# hc-isp-echo.net
KiCad netlist of a schematic drawn in EAGLE
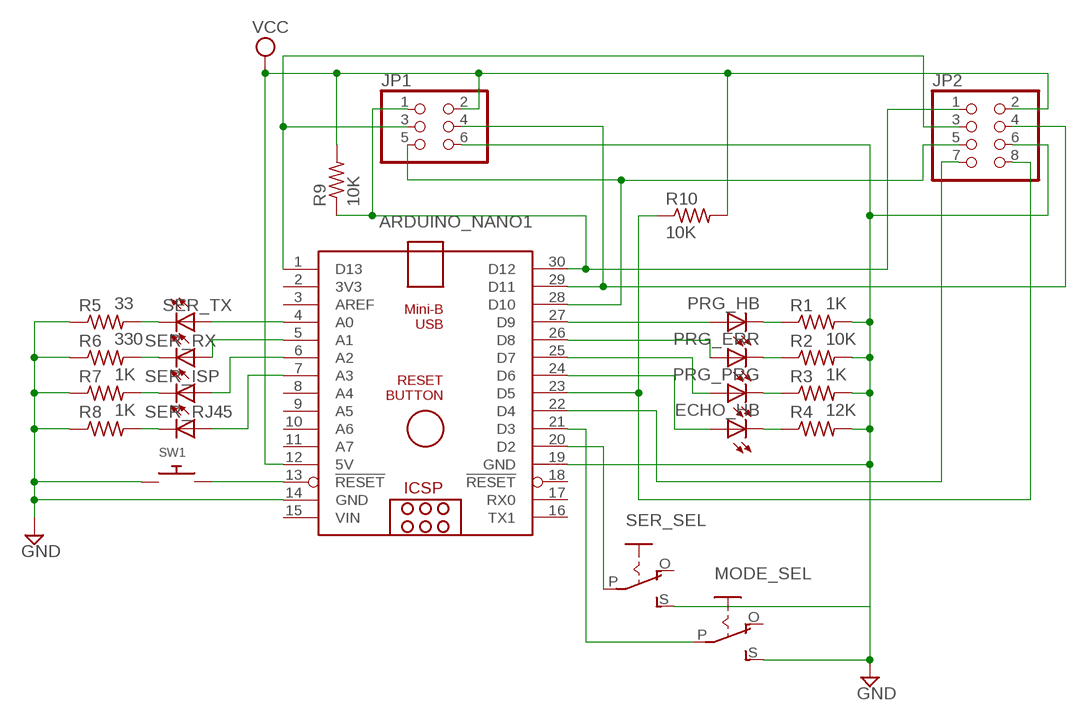
[diagram p0: schematic, sheet 1]

(export (version "E")
  (design (tool "Eeschema 10.0.6"))
  (components
    (comp (ref "ARDUINO_NANO1")
      (value "ARDUINO_NANO_HCARDUINO_NANO_NO_HOLE")
      (footprint "eagle-import:ARDUINO_NANO_NO_HOLE")
      (libsource (lib "eagle-import") (part "ARDUINO_NANO_HCARDUINO_NANO_NO_HOLE"))
    )
    (comp (ref "ECHO_HB")
      (value "LED5MM")
      (footprint "eagle-import:LED5MM")
      (libsource (lib "eagle-import") (part "LED5MM"))
    )
    (comp (ref "JP1")
      (value "PINHD-2X3")
      (footprint "eagle-import:2X03")
      (libsource (lib "eagle-import") (part "PINHD-2X3"))
    )
    (comp (ref "JP2")
      (value "PINHD-2X4")
      (footprint "eagle-import:2X04")
      (libsource (lib "eagle-import") (part "PINHD-2X4"))
    )
    (comp (ref "MODE_SEL")
      (value "EG1218S")
      (footprint "eagle-import:EG1218")
      (libsource (lib "eagle-import") (part "EG1218S"))
    )
    (comp (ref "PRG_ERR")
      (value "LED5MM")
      (footprint "eagle-import:LED5MM")
      (libsource (lib "eagle-import") (part "LED5MM"))
    )
    (comp (ref "PRG_HB")
      (value "LED5MM")
      (footprint "eagle-import:LED5MM")
      (libsource (lib "eagle-import") (part "LED5MM"))
    )
    (comp (ref "PRG_PRG")
      (value "LED5MM")
      (footprint "eagle-import:LED5MM")
      (libsource (lib "eagle-import") (part "LED5MM"))
    )
    (comp (ref "R1")
      (value "1K")
      (footprint "eagle-import:0309_12")
      (libsource (lib "eagle-import") (part "R-US_0309/12"))
    )
    (comp (ref "R2")
      (value "10K")
      (footprint "eagle-import:0309_12")
      (libsource (lib "eagle-import") (part "R-US_0309/12"))
    )
    (comp (ref "R3")
      (value "1K")
      (footprint "eagle-import:0309_12")
      (libsource (lib "eagle-import") (part "R-US_0309/12"))
    )
    (comp (ref "R4")
      (value "12K")
      (footprint "eagle-import:0309_12")
      (libsource (lib "eagle-import") (part "R-US_0309/12"))
    )
    (comp (ref "R5")
      (value "33")
      (footprint "eagle-import:0309_12")
      (libsource (lib "eagle-import") (part "R-US_0309/12"))
    )
    (comp (ref "R6")
      (value "330")
      (footprint "eagle-import:0309_12")
      (libsource (lib "eagle-import") (part "R-US_0309/12"))
    )
    (comp (ref "R7")
      (value "1K")
      (footprint "eagle-import:0309_12")
      (libsource (lib "eagle-import") (part "R-US_0309/12"))
    )
    (comp (ref "R8")
      (value "1K")
      (footprint "eagle-import:0309_12")
      (libsource (lib "eagle-import") (part "R-US_0309/12"))
    )
    (comp (ref "R9")
      (value "10K")
      (footprint "eagle-import:0309_12")
      (libsource (lib "eagle-import") (part "R-US_0309/12"))
    )
    (comp (ref "R10")
      (value "10K")
      (footprint "eagle-import:0309_12")
      (libsource (lib "eagle-import") (part "R-US_0309/12"))
    )
    (comp (ref "SER_ISP")
      (value "LED5MM")
      (footprint "eagle-import:LED5MM")
      (libsource (lib "eagle-import") (part "LED5MM"))
    )
    (comp (ref "SER_RJ45")
      (value "LED5MM")
      (footprint "eagle-import:LED5MM")
      (libsource (lib "eagle-import") (part "LED5MM"))
    )
    (comp (ref "SER_RX")
      (value "LED5MM")
      (footprint "eagle-import:LED5MM")
      (libsource (lib "eagle-import") (part "LED5MM"))
    )
    (comp (ref "SER_SEL")
      (value "EG1218S")
      (footprint "eagle-import:EG1218")
      (libsource (lib "eagle-import") (part "EG1218S"))
    )
    (comp (ref "SER_TX")
      (value "LED5MM")
      (footprint "eagle-import:LED5MM")
      (libsource (lib "eagle-import") (part "LED5MM"))
    )
    (comp (ref "SW1")
      (value "SWITCH_PUSHBUTTONEVQ-PE")
      (footprint "eagle-import:TACT_PANA-EVQ")
      (libsource (lib "eagle-import") (part "SWITCH_PUSHBUTTONEVQ-PE"))
    )
  )
  (nets
    (net (code "1") (name "/VIN") (class "Default")
      (node (ref "ARDUINO_NANO1") (pin "15") (pinfunction "VIN_15") (pintype "power_in"))
    )
    (net (code "2") (name "GND") (class "Default")
      (node (ref "ARDUINO_NANO1") (pin "14") (pinfunction "GND_14") (pintype "power_in"))
      (node (ref "ARDUINO_NANO1") (pin "19") (pinfunction "GND_19") (pintype "power_in"))
      (node (ref "JP1") (pin "6") (pinfunction "6_6") (pintype "passive"))
      (node (ref "JP2") (pin "6") (pinfunction "6_6") (pintype "passive"))
      (node (ref "MODE_SEL") (pin "S") (pinfunction "S_S") (pintype "passive"))
      (node (ref "R1") (pin "2") (pinfunction "2_2") (pintype "passive"))
      (node (ref "R2") (pin "2") (pinfunction "2_2") (pintype "passive"))
      (node (ref "R3") (pin "2") (pinfunction "2_2") (pintype "passive"))
      (node (ref "R4") (pin "2") (pinfunction "2_2") (pintype "passive"))
      (node (ref "R5") (pin "1") (pinfunction "1_1") (pintype "passive"))
      (node (ref "R6") (pin "1") (pinfunction "1_1") (pintype "passive"))
      (node (ref "R7") (pin "1") (pinfunction "1_1") (pintype "passive"))
      (node (ref "R8") (pin "1") (pinfunction "1_1") (pintype "passive"))
      (node (ref "SER_SEL") (pin "S") (pinfunction "S_S") (pintype "passive"))
      (node (ref "SW1") (pin "P$1") (pinfunction "P$1_P$1") (pintype "passive"))
    )
    (net (code "3") (name "Net-(ARDUINO_NANO1-A0)") (class "Default")
      (node (ref "ARDUINO_NANO1") (pin "4") (pinfunction "A0_4") (pintype "bidirectional"))
      (node (ref "SER_TX") (pin "A") (pinfunction "A_A") (pintype "passive"))
    )
    (net (code "4") (name "Net-(ARDUINO_NANO1-A1)") (class "Default")
      (node (ref "ARDUINO_NANO1") (pin "5") (pinfunction "A1_5") (pintype "bidirectional"))
      (node (ref "SER_RX") (pin "A") (pinfunction "A_A") (pintype "passive"))
    )
    (net (code "5") (name "Net-(ARDUINO_NANO1-A2)") (class "Default")
      (node (ref "ARDUINO_NANO1") (pin "6") (pinfunction "A2_6") (pintype "bidirectional"))
      (node (ref "SER_ISP") (pin "A") (pinfunction "A_A") (pintype "passive"))
    )
    (net (code "6") (name "Net-(ARDUINO_NANO1-A3)") (class "Default")
      (node (ref "ARDUINO_NANO1") (pin "7") (pinfunction "A3_7") (pintype "bidirectional"))
      (node (ref "SER_RJ45") (pin "A") (pinfunction "A_A") (pintype "passive"))
    )
    (net (code "7") (name "Net-(ARDUINO_NANO1-D2)") (class "Default")
      (node (ref "ARDUINO_NANO1") (pin "20") (pinfunction "D2_20") (pintype "bidirectional"))
      (node (ref "SER_SEL") (pin "P") (pinfunction "P_P") (pintype "passive"))
    )
    (net (code "8") (name "Net-(ARDUINO_NANO1-D3)") (class "Default")
      (node (ref "ARDUINO_NANO1") (pin "21") (pinfunction "D3_21") (pintype "bidirectional"))
      (node (ref "MODE_SEL") (pin "P") (pinfunction "P_P") (pintype "passive"))
    )
    (net (code "9") (name "Net-(ARDUINO_NANO1-D4)") (class "Default")
      (node (ref "ARDUINO_NANO1") (pin "22") (pinfunction "D4_22") (pintype "bidirectional"))
      (node (ref "JP2") (pin "7") (pinfunction "7_7") (pintype "passive"))
    )
    (net (code "10") (name "Net-(ARDUINO_NANO1-D5)") (class "Default")
      (node (ref "ARDUINO_NANO1") (pin "23") (pinfunction "D5_23") (pintype "bidirectional"))
      (node (ref "JP2") (pin "8") (pinfunction "8_8") (pintype "passive"))
      (node (ref "R10") (pin "1") (pinfunction "1_1") (pintype "passive"))
    )
    (net (code "11") (name "Net-(ARDUINO_NANO1-D6)") (class "Default")
      (node (ref "ARDUINO_NANO1") (pin "24") (pinfunction "D6_24") (pintype "bidirectional"))
      (node (ref "ECHO_HB") (pin "A") (pinfunction "A_A") (pintype "passive"))
    )
    (net (code "12") (name "Net-(ARDUINO_NANO1-D7)") (class "Default")
      (node (ref "ARDUINO_NANO1") (pin "25") (pinfunction "D7_25") (pintype "bidirectional"))
      (node (ref "PRG_PRG") (pin "A") (pinfunction "A_A") (pintype "passive"))
    )
    (net (code "13") (name "Net-(ARDUINO_NANO1-D8)") (class "Default")
      (node (ref "ARDUINO_NANO1") (pin "26") (pinfunction "D8_26") (pintype "bidirectional"))
      (node (ref "PRG_ERR") (pin "A") (pinfunction "A_A") (pintype "passive"))
    )
    (net (code "14") (name "Net-(ARDUINO_NANO1-D9)") (class "Default")
      (node (ref "ARDUINO_NANO1") (pin "27") (pinfunction "D9_27") (pintype "bidirectional"))
      (node (ref "PRG_HB") (pin "A") (pinfunction "A_A") (pintype "passive"))
    )
    (net (code "15") (name "Net-(ARDUINO_NANO1-D10)") (class "Default")
      (node (ref "ARDUINO_NANO1") (pin "28") (pinfunction "D10_28") (pintype "bidirectional"))
      (node (ref "JP1") (pin "5") (pinfunction "5_5") (pintype "passive"))
      (node (ref "JP2") (pin "5") (pinfunction "5_5") (pintype "passive"))
    )
    (net (code "16") (name "Net-(ARDUINO_NANO1-D11)") (class "Default")
      (node (ref "ARDUINO_NANO1") (pin "29") (pinfunction "D11_29") (pintype "bidirectional"))
      (node (ref "JP1") (pin "4") (pinfunction "4_4") (pintype "passive"))
      (node (ref "JP2") (pin "4") (pinfunction "4_4") (pintype "passive"))
    )
    (net (code "17") (name "Net-(ARDUINO_NANO1-D12)") (class "Default")
      (node (ref "ARDUINO_NANO1") (pin "30") (pinfunction "D12_30") (pintype "bidirectional"))
      (node (ref "JP1") (pin "1") (pinfunction "1_1") (pintype "passive"))
      (node (ref "JP2") (pin "1") (pinfunction "1_1") (pintype "passive"))
      (node (ref "R9") (pin "1") (pinfunction "1_1") (pintype "passive"))
    )
    (net (code "18") (name "Net-(ARDUINO_NANO1-D13)") (class "Default")
      (node (ref "ARDUINO_NANO1") (pin "1") (pinfunction "D13_1") (pintype "bidirectional"))
      (node (ref "JP1") (pin "3") (pinfunction "3_3") (pintype "passive"))
      (node (ref "JP2") (pin "3") (pinfunction "3_3") (pintype "passive"))
    )
    (net (code "19") (name "Net-(ARDUINO_NANO1-~{RESET}-Pad13)") (class "Default")
      (node (ref "ARDUINO_NANO1") (pin "13") (pinfunction "~{RESET}_13") (pintype "input"))
      (node (ref "SW1") (pin "P$2") (pinfunction "P$2_P$2") (pintype "passive"))
    )
    (net (code "20") (name "Net-(ECHO_HB-C)") (class "Default")
      (node (ref "ECHO_HB") (pin "K") (pinfunction "C_K") (pintype "passive"))
      (node (ref "R4") (pin "1") (pinfunction "1_1") (pintype "passive"))
    )
    (net (code "21") (name "Net-(PRG_ERR-C)") (class "Default")
      (node (ref "PRG_ERR") (pin "K") (pinfunction "C_K") (pintype "passive"))
      (node (ref "R2") (pin "1") (pinfunction "1_1") (pintype "passive"))
    )
    (net (code "22") (name "Net-(PRG_HB-C)") (class "Default")
      (node (ref "PRG_HB") (pin "K") (pinfunction "C_K") (pintype "passive"))
      (node (ref "R1") (pin "1") (pinfunction "1_1") (pintype "passive"))
    )
    (net (code "23") (name "Net-(PRG_PRG-C)") (class "Default")
      (node (ref "PRG_PRG") (pin "K") (pinfunction "C_K") (pintype "passive"))
      (node (ref "R3") (pin "1") (pinfunction "1_1") (pintype "passive"))
    )
    (net (code "24") (name "Net-(SER_ISP-C)") (class "Default")
      (node (ref "R7") (pin "2") (pinfunction "2_2") (pintype "passive"))
      (node (ref "SER_ISP") (pin "K") (pinfunction "C_K") (pintype "passive"))
    )
    (net (code "25") (name "Net-(SER_RJ45-C)") (class "Default")
      (node (ref "R8") (pin "2") (pinfunction "2_2") (pintype "passive"))
      (node (ref "SER_RJ45") (pin "K") (pinfunction "C_K") (pintype "passive"))
    )
    (net (code "26") (name "Net-(SER_RX-C)") (class "Default")
      (node (ref "R6") (pin "2") (pinfunction "2_2") (pintype "passive"))
      (node (ref "SER_RX") (pin "K") (pinfunction "C_K") (pintype "passive"))
    )
    (net (code "27") (name "Net-(SER_TX-C)") (class "Default")
      (node (ref "R5") (pin "2") (pinfunction "2_2") (pintype "passive"))
      (node (ref "SER_TX") (pin "K") (pinfunction "C_K") (pintype "passive"))
    )
    (net (code "28") (name "VCC") (class "Default")
      (node (ref "ARDUINO_NANO1") (pin "12") (pinfunction "5V_12") (pintype "power_in"))
      (node (ref "JP1") (pin "2") (pinfunction "2_2") (pintype "passive"))
      (node (ref "JP2") (pin "2") (pinfunction "2_2") (pintype "passive"))
      (node (ref "R10") (pin "2") (pinfunction "2_2") (pintype "passive"))
      (node (ref "R9") (pin "2") (pinfunction "2_2") (pintype "passive"))
    )
    (net (code "29") (name "unconnected-(ARDUINO_NANO1-3V3-Pad2)") (class "Default")
      (node (ref "ARDUINO_NANO1") (pin "2") (pinfunction "3V3_2") (pintype "output"))
    )
    (net (code "30") (name "unconnected-(ARDUINO_NANO1-A4-Pad8)") (class "Default")
      (node (ref "ARDUINO_NANO1") (pin "8") (pinfunction "A4_8") (pintype "bidirectional"))
    )
    (net (code "31") (name "unconnected-(ARDUINO_NANO1-A5-Pad9)") (class "Default")
      (node (ref "ARDUINO_NANO1") (pin "9") (pinfunction "A5_9") (pintype "bidirectional"))
    )
    (net (code "32") (name "unconnected-(ARDUINO_NANO1-A6-Pad10)") (class "Default")
      (node (ref "ARDUINO_NANO1") (pin "10") (pinfunction "A6_10") (pintype "bidirectional"))
    )
    (net (code "33") (name "unconnected-(ARDUINO_NANO1-A7-Pad11)") (class "Default")
      (node (ref "ARDUINO_NANO1") (pin "11") (pinfunction "A7_11") (pintype "bidirectional"))
    )
    (net (code "34") (name "unconnected-(ARDUINO_NANO1-AREF-Pad3)") (class "Default")
      (node (ref "ARDUINO_NANO1") (pin "3") (pinfunction "AREF_3") (pintype "input"))
    )
    (net (code "35") (name "unconnected-(ARDUINO_NANO1-RX0-Pad17)") (class "Default")
      (node (ref "ARDUINO_NANO1") (pin "17") (pinfunction "RX0_17") (pintype "bidirectional"))
    )
    (net (code "36") (name "unconnected-(ARDUINO_NANO1-TX1-Pad16)") (class "Default")
      (node (ref "ARDUINO_NANO1") (pin "16") (pinfunction "TX1_16") (pintype "bidirectional"))
    )
    (net (code "37") (name "unconnected-(ARDUINO_NANO1-~{RESET}-Pad18)") (class "Default")
      (node (ref "ARDUINO_NANO1") (pin "18") (pinfunction "~{RESET}_18") (pintype "input"))
    )
    (net (code "38") (name "unconnected-(MODE_SEL-PadO)") (class "Default")
      (node (ref "MODE_SEL") (pin "O") (pinfunction "O_O") (pintype "passive"))
    )
    (net (code "39") (name "unconnected-(SER_SEL-PadO)") (class "Default")
      (node (ref "SER_SEL") (pin "O") (pinfunction "O_O") (pintype "passive"))
    )
  )
)
